# NOT_GATE.net
KiCad netlist of a schematic drawn in EAGLE
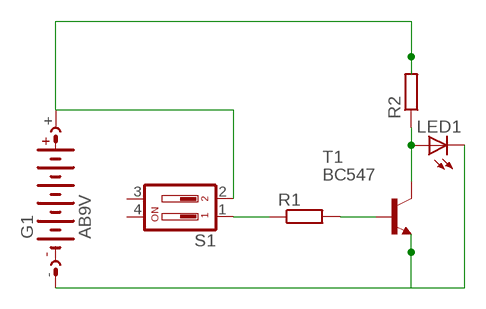
[diagram p0: schematic, sheet 1]

(export (version "E")
  (design (tool "Eeschema 10.0.6"))
  (components
    (comp (ref "G1")
      (value "AB9V")
      (footprint "eagle-import:AB9V")
      (libsource (lib "eagle-import") (part "AB9V"))
    )
    (comp (ref "LED1")
      (value "LED5MM")
      (footprint "eagle-import:LED5MM")
      (libsource (lib "eagle-import") (part "LED5MM"))
    )
    (comp (ref "R1")
      (value "R-EU_0204/7")
      (footprint "eagle-import:0204_7")
      (libsource (lib "eagle-import") (part "R-EU_0204/7"))
    )
    (comp (ref "R2")
      (value "R-EU_0204/7")
      (footprint "eagle-import:0204_7")
      (libsource (lib "eagle-import") (part "R-EU_0204/7"))
    )
    (comp (ref "S1")
      (value "DS02")
      (footprint "eagle-import:DS-02")
      (libsource (lib "eagle-import") (part "DS02"))
    )
    (comp (ref "T1")
      (value "BC547")
      (footprint "eagle-import:TO92")
      (libsource (lib "eagle-import") (part "BC547"))
    )
  )
  (nets
    (net (code "1") (name "Net-(G1-Pad+)") (class "Default")
      (node (ref "G1") (pin "+") (pinfunction "+_+") (pintype "passive"))
      (node (ref "R2") (pin "2") (pinfunction "2_2") (pintype "passive"))
      (node (ref "S1") (pin "2") (pinfunction "2_2") (pintype "passive"))
    )
    (net (code "2") (name "Net-(LED1-C)") (class "Default")
      (node (ref "G1") (pin "-") (pinfunction "-_-") (pintype "passive"))
      (node (ref "LED1") (pin "K") (pinfunction "C_K") (pintype "passive"))
      (node (ref "T1") (pin "1") (pinfunction "E_1") (pintype "passive"))
    )
    (net (code "3") (name "Net-(R1-Pad1)") (class "Default")
      (node (ref "R1") (pin "1") (pinfunction "1_1") (pintype "passive"))
      (node (ref "S1") (pin "1") (pinfunction "1_1") (pintype "passive"))
    )
    (net (code "4") (name "Net-(T1-B)") (class "Default")
      (node (ref "R1") (pin "2") (pinfunction "2_2") (pintype "passive"))
      (node (ref "T1") (pin "2") (pinfunction "B_2") (pintype "passive"))
    )
    (net (code "5") (name "Net-(T1-C)") (class "Default")
      (node (ref "LED1") (pin "A") (pinfunction "A_A") (pintype "passive"))
      (node (ref "R2") (pin "1") (pinfunction "1_1") (pintype "passive"))
      (node (ref "T1") (pin "3") (pinfunction "C_3") (pintype "passive"))
    )
    (net (code "6") (name "unconnected-(S1-Pad3)") (class "Default")
      (node (ref "S1") (pin "3") (pinfunction "3_3") (pintype "passive"))
    )
    (net (code "7") (name "unconnected-(S1-Pad4)") (class "Default")
      (node (ref "S1") (pin "4") (pinfunction "4_4") (pintype "passive"))
    )
  )
)
